# memory.net
KiCad netlist of a schematic drawn in Altium Designer
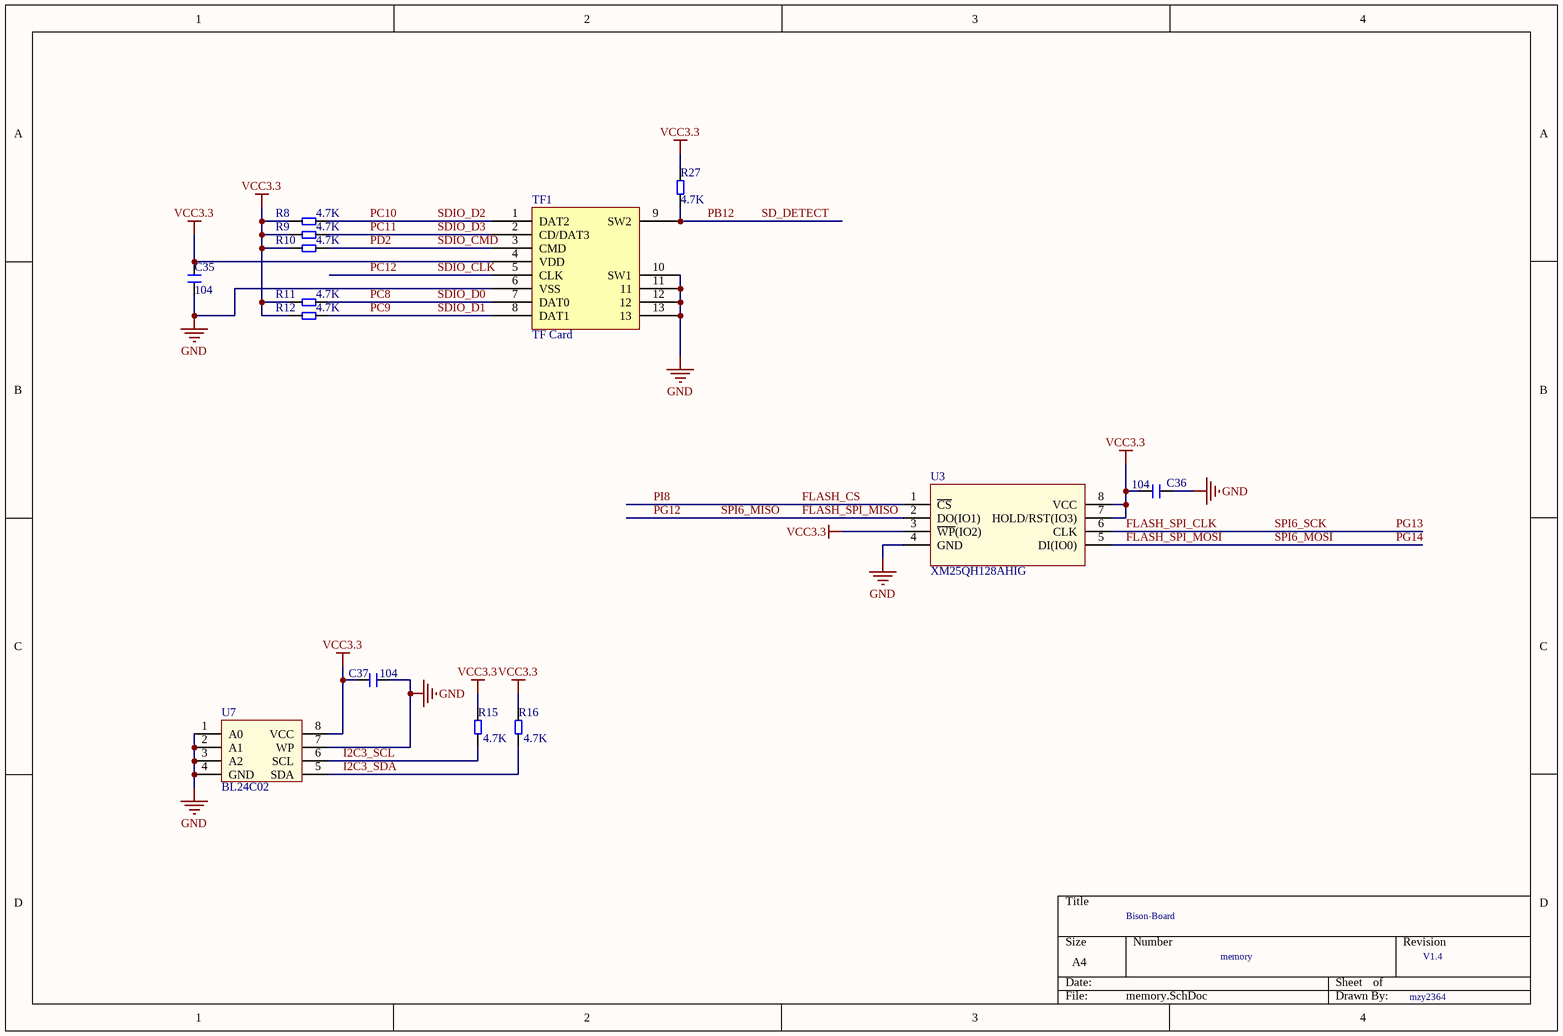
[diagram p0: memory.SchDoc]

(export (version "E")
  (design (tool "Eeschema 10.0.6"))
  (components
    (comp (ref "C35") (value "104") (footprint "C 0603") (libsource (lib "Bison-Board") (part "CAP")))
    (comp (ref "C36") (value "104") (footprint "C 0603") (libsource (lib "Bison-Board") (part "CAP")))
    (comp (ref "C37") (value "104") (footprint "C 0603") (libsource (lib "Bison-Board") (part "CAP")))
    (comp (ref "R8") (value "4.7K") (footprint "R 0603") (libsource (lib "Bison-Board") (part "RES")))
    (comp (ref "R9") (value "4.7K") (footprint "R 0603") (libsource (lib "Bison-Board") (part "RES")))
    (comp (ref "R10") (value "4.7K") (footprint "R 0603") (libsource (lib "Bison-Board") (part "RES")))
    (comp (ref "R11") (value "4.7K") (footprint "R 0603") (libsource (lib "Bison-Board") (part "RES")))
    (comp (ref "R12") (value "4.7K") (footprint "R 0603") (libsource (lib "Bison-Board") (part "RES")))
    (comp (ref "R15") (value "4.7K") (footprint "R 0603") (libsource (lib "Bison-Board") (part "RES")))
    (comp (ref "R16") (value "4.7K") (footprint "R 0603") (libsource (lib "Bison-Board") (part "RES")))
    (comp (ref "R27") (value "4.7K") (footprint "R 0603") (libsource (lib "Bison-Board") (part "RES")))
    (comp (ref "TF1")
      (value "TF Card")
      (footprint "TF Card")
      (libsource (lib "Bison-Board") (part "TF Card"))
    )
    (comp (ref "U3")
      (value "XM25QH128AHIG")
      (footprint "SOIC-8-208mil")
      (libsource (lib "Bison-Board") (part "W25Q128"))
    )
    (comp (ref "U7") (value "BL24C02") (footprint "SOP8") (libsource (lib "Bison-Board") (part "24C02")))
  )
  (nets
    (net (code "1") (name "/FLASH_CS") (class "Default")
      (node (ref "U3") (pin "1") (pinfunction "~{CS}_1") (pintype "passive"))
    )
    (net (code "2") (name "/FLASH_SPI_CLK") (class "Default")
      (node (ref "U3") (pin "6") (pinfunction "CLK_6") (pintype "passive"))
    )
    (net (code "3") (name "/FLASH_SPI_MISO") (class "Default")
      (node (ref "U3") (pin "2") (pinfunction "DO(IO1)_2") (pintype "passive"))
    )
    (net (code "4") (name "/FLASH_SPI_MOSI") (class "Default")
      (node (ref "U3") (pin "5") (pinfunction "DI(IO0)_5") (pintype "passive"))
    )
    (net (code "5") (name "/I2C3_SCL") (class "Default")
      (node (ref "R15") (pin "1") (pintype "passive"))
      (node (ref "U7") (pin "6") (pinfunction "SCL_6") (pintype "passive"))
    )
    (net (code "6") (name "/I2C3_SDA") (class "Default")
      (node (ref "R16") (pin "1") (pintype "passive"))
      (node (ref "U7") (pin "5") (pinfunction "SDA_5") (pintype "passive"))
    )
    (net (code "7") (name "/PB12") (class "Default")
      (node (ref "R27") (pin "1") (pintype "passive"))
      (node (ref "TF1") (pin "9") (pinfunction "SW2_9") (pintype "passive"))
    )
    (net (code "8") (name "/PC8") (class "Default")
      (node (ref "R11") (pin "2") (pintype "passive"))
      (node (ref "TF1") (pin "7") (pinfunction "DAT0_7") (pintype "passive"))
    )
    (net (code "9") (name "/PC9") (class "Default")
      (node (ref "R12") (pin "2") (pintype "passive"))
      (node (ref "TF1") (pin "8") (pinfunction "DAT1_8") (pintype "passive"))
    )
    (net (code "10") (name "/PC10") (class "Default")
      (node (ref "R8") (pin "2") (pintype "passive"))
      (node (ref "TF1") (pin "1") (pinfunction "DAT2_1") (pintype "passive"))
    )
    (net (code "11") (name "/PC11") (class "Default")
      (node (ref "R9") (pin "2") (pintype "passive"))
      (node (ref "TF1") (pin "2") (pinfunction "CD/DAT3_2") (pintype "passive"))
    )
    (net (code "12") (name "/PC12") (class "Default")
      (node (ref "TF1") (pin "5") (pinfunction "CLK_5") (pintype "passive"))
    )
    (net (code "13") (name "/PD2") (class "Default")
      (node (ref "R10") (pin "2") (pintype "passive"))
      (node (ref "TF1") (pin "3") (pinfunction "CMD_3") (pintype "passive"))
    )
    (net (code "14") (name "GND") (class "Default")
      (node (ref "C35") (pin "1") (pinfunction "1_1") (pintype "passive"))
      (node (ref "C36") (pin "2") (pinfunction "2_2") (pintype "passive"))
      (node (ref "C37") (pin "2") (pinfunction "2_2") (pintype "passive"))
      (node (ref "TF1") (pin "10") (pinfunction "SW1_10") (pintype "passive"))
      (node (ref "TF1") (pin "11") (pinfunction "11_11") (pintype "passive"))
      (node (ref "TF1") (pin "12") (pinfunction "12_12") (pintype "passive"))
      (node (ref "TF1") (pin "13") (pinfunction "13_13") (pintype "passive"))
      (node (ref "TF1") (pin "6") (pinfunction "VSS_6") (pintype "passive"))
      (node (ref "U3") (pin "4") (pinfunction "GND_4") (pintype "passive"))
      (node (ref "U7") (pin "1") (pinfunction "A0_1") (pintype "passive"))
      (node (ref "U7") (pin "2") (pinfunction "A1_2") (pintype "passive"))
      (node (ref "U7") (pin "3") (pinfunction "A2_3") (pintype "passive"))
      (node (ref "U7") (pin "4") (pinfunction "GND_4") (pintype "passive"))
      (node (ref "U7") (pin "7") (pinfunction "WP_7") (pintype "passive"))
    )
    (net (code "15") (name "VCC3.3") (class "Default")
      (node (ref "C35") (pin "2") (pinfunction "2_2") (pintype "passive"))
      (node (ref "C36") (pin "1") (pinfunction "1_1") (pintype "passive"))
      (node (ref "C37") (pin "1") (pinfunction "1_1") (pintype "passive"))
      (node (ref "R10") (pin "1") (pintype "passive"))
      (node (ref "R11") (pin "1") (pintype "passive"))
      (node (ref "R12") (pin "1") (pintype "passive"))
      (node (ref "R15") (pin "2") (pintype "passive"))
      (node (ref "R16") (pin "2") (pintype "passive"))
      (node (ref "R27") (pin "2") (pintype "passive"))
      (node (ref "R8") (pin "1") (pintype "passive"))
      (node (ref "R9") (pin "1") (pintype "passive"))
      (node (ref "TF1") (pin "4") (pinfunction "VDD_4") (pintype "passive"))
      (node (ref "U3") (pin "3") (pinfunction "~{WP}(IO2)_3") (pintype "passive"))
      (node (ref "U3") (pin "7") (pinfunction "HOLD/RST(IO3)_7") (pintype "passive"))
      (node (ref "U3") (pin "8") (pinfunction "VCC_8") (pintype "passive"))
      (node (ref "U7") (pin "8") (pinfunction "VCC_8") (pintype "passive"))
    )
  )
)
